# Fastino_DIOT_Connectors_P1_P6.net
KiCad netlist of a schematic drawn in Altium Designer
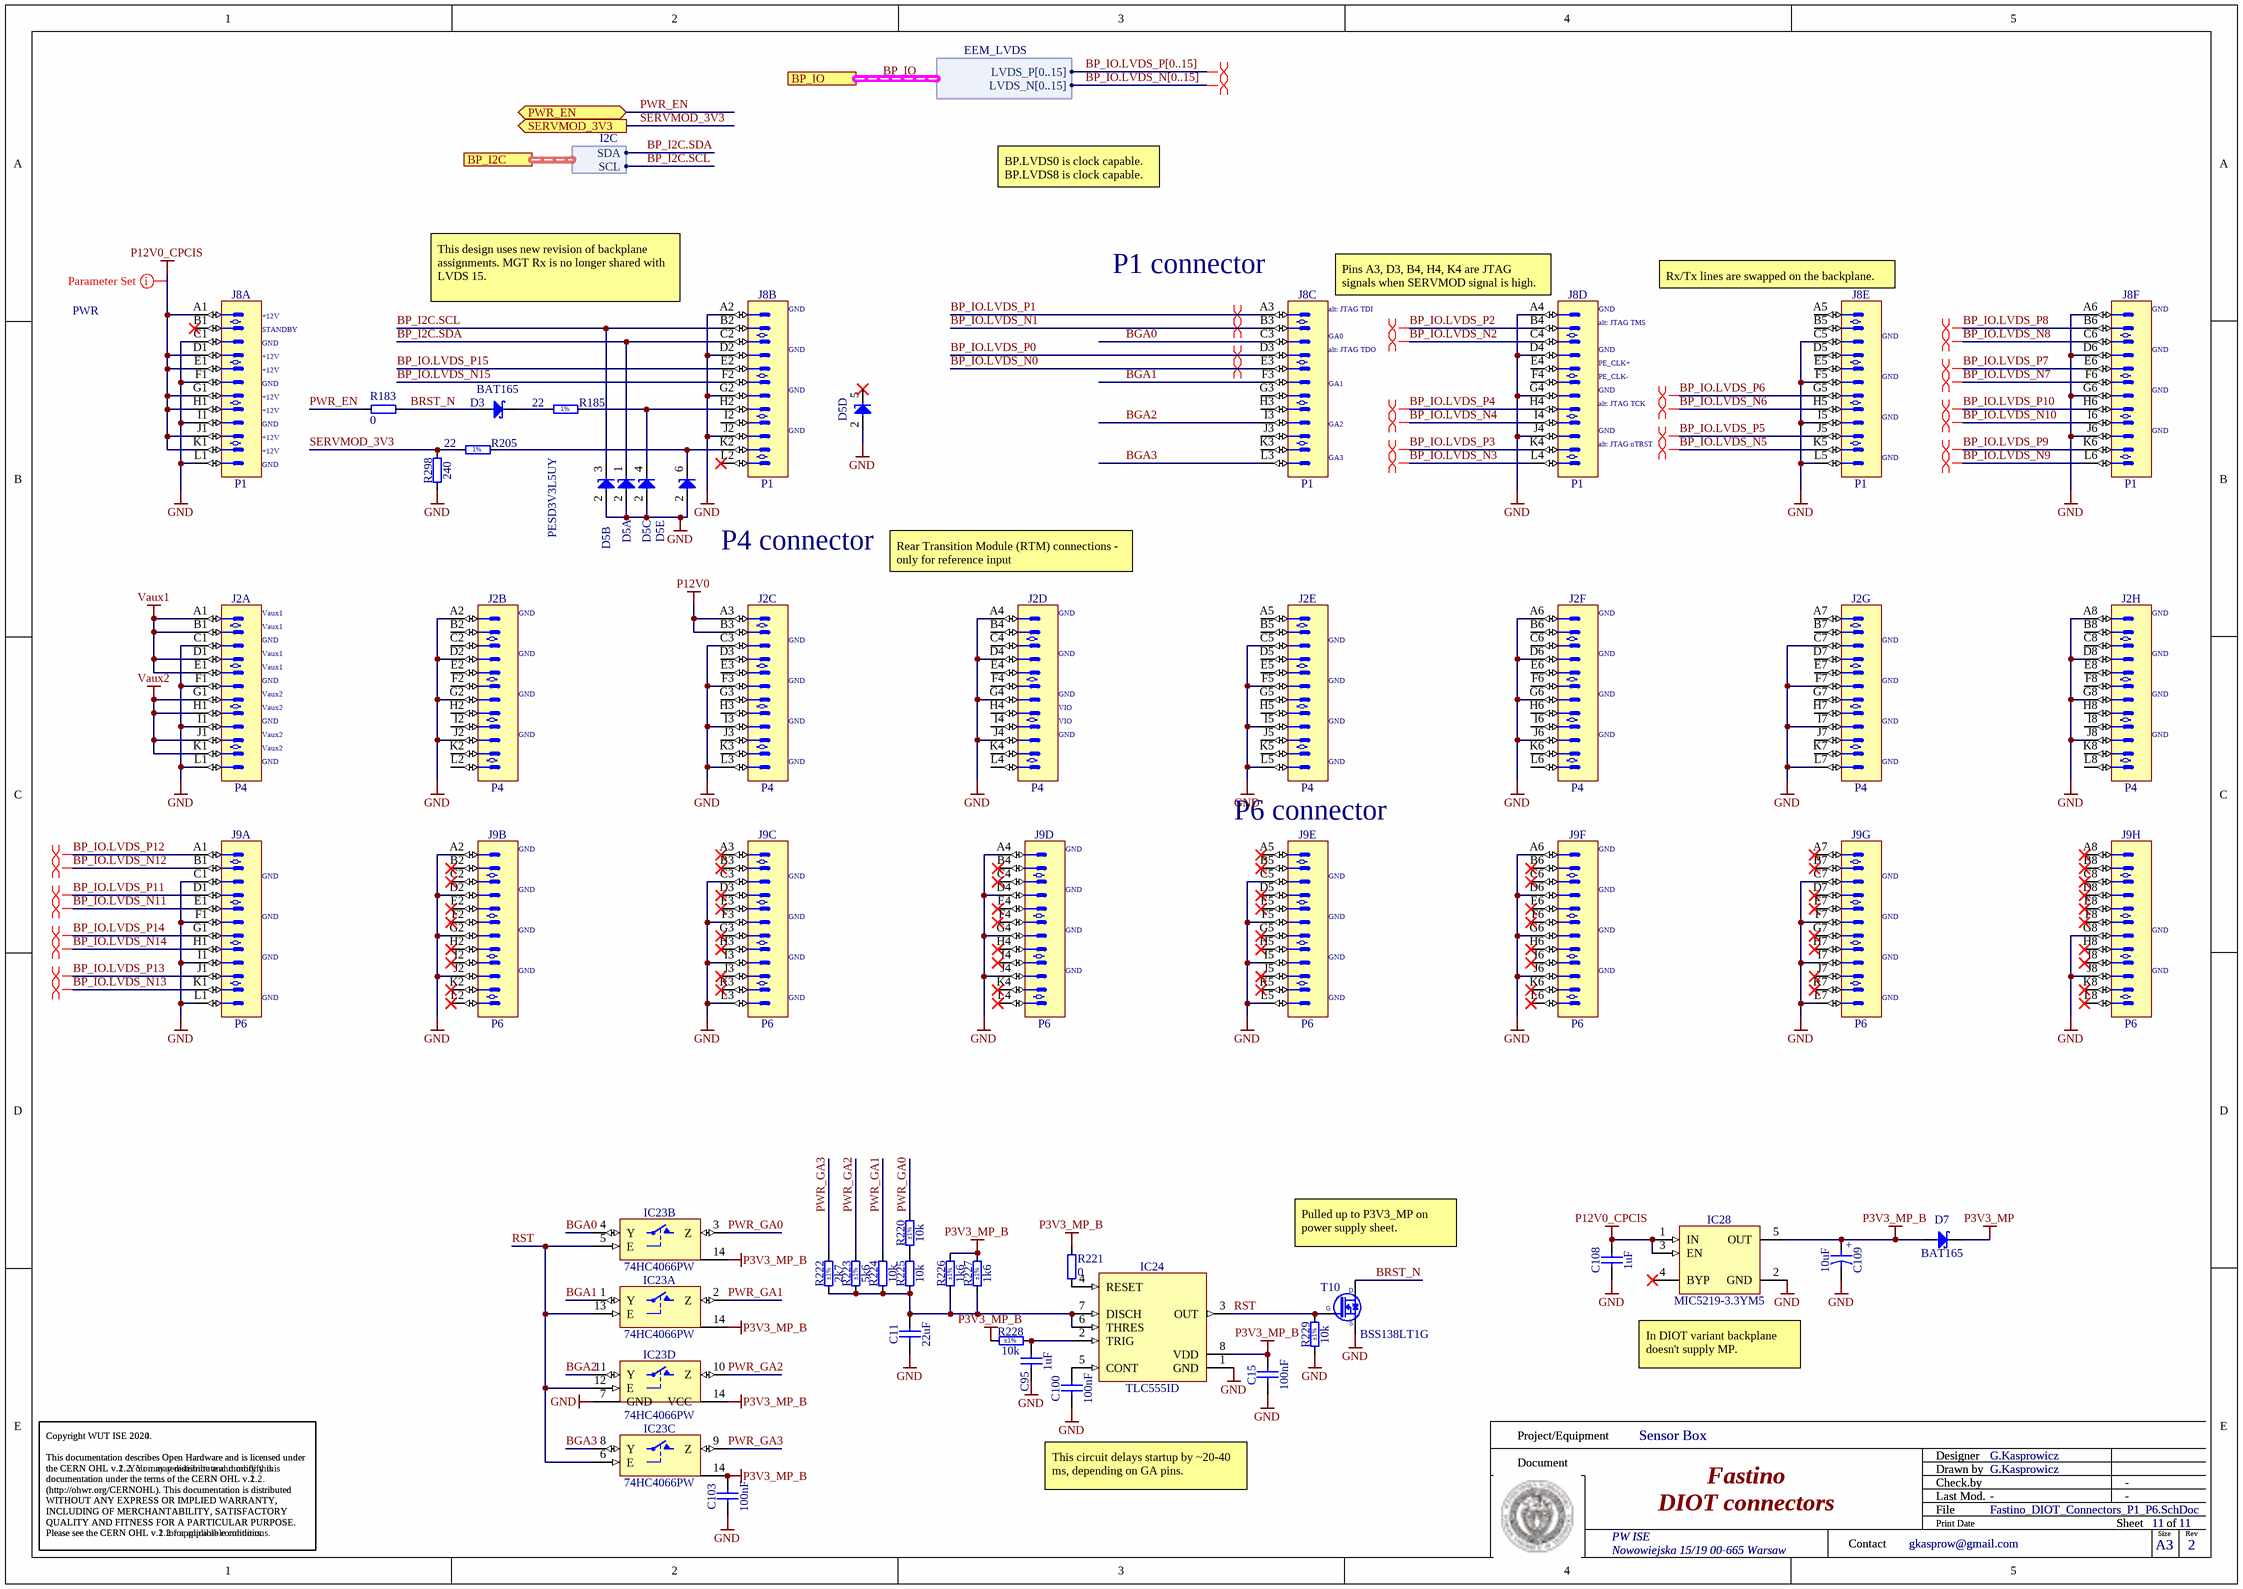
[diagram p0: Fastino_DIOT_Connectors_P1_P6.SchDoc]

(export (version "E")
  (design (tool "Eeschema 10.0.6"))
  (components
    (comp (ref "C11")
      (value "22uF")
      (footprint "CAPC1608X90N")
      (description "Non-polarised capacitor")
      (fields
        (field (name "MANUFACTURER") "GENERIC")
        (field (name "PART NUMBER") "CC0603_22UF_6.3V_20%_X5R")
        (field (name "AUTHOR") "CERN DEM JLC")
      )
      (libsource (lib "Capacitors") (part "Capacitor - non polarized"))
    )
    (comp (ref "C15")
      (value "100nF")
      (footprint "CAPC1005X55N")
      (description "Non-polarised capacitor")
      (fields
        (field (name "PART NUMBER") "CC0402_100NF_16V_10%_X5R")
        (field (name "VOLTAGE") "16V")
        (field (name "AUTHOR") "CERN DEM JLC")
      )
      (libsource (lib "Capacitors") (part "Capacitor - non polarized"))
    )
    (comp (ref "C95")
      (value "1uF")
      (footprint "CAPC1005X55N")
      (description "Non-polarised capacitor")
      (fields
        (field (name "PART NUMBER") "CC0402_1UF_16V_10%_X5R")
        (field (name "VOLTAGE") "16V")
        (field (name "AUTHOR") "CERN DEM JLC")
      )
      (libsource (lib "Capacitors") (part "Capacitor - non polarized"))
    )
    (comp (ref "C100")
      (value "100nF")
      (footprint "CAPC1005X55N")
      (description "Non-polarised capacitor")
      (fields
        (field (name "PART NUMBER") "CC0402_100NF_16V_10%_X5R")
        (field (name "VOLTAGE") "16V")
        (field (name "AUTHOR") "CERN DEM JLC")
      )
      (libsource (lib "Capacitors") (part "Capacitor - non polarized"))
    )
    (comp (ref "C103")
      (value "100nF")
      (footprint "CAPC1005X55N")
      (description "Non-polarised capacitor")
      (fields
        (field (name "PART NUMBER") "CC0402_100NF_16V_10%_X5R")
        (field (name "VOLTAGE") "16V")
        (field (name "AUTHOR") "CERN DEM JLC")
      )
      (libsource (lib "Capacitors") (part "Capacitor - non polarized"))
    )
    (comp (ref "C108")
      (value "1uF")
      (footprint "CAPC1608X87N")
      (description "Non-polarised capacitor")
      (fields
        (field (name "PART NUMBER") "CC0603_1UF_25V_10%_X7R")
        (field (name "VOLTAGE") "25V")
        (field (name "AUTHOR") "CERN DEM JLC")
      )
      (libsource (lib "Capacitors") (part "Capacitor - non polarized"))
    )
    (comp (ref "C109")
      (value "10uF")
      (footprint "CAPMP3216X180N")
      (description "Polarised capacitor")
      (fields
        (field (name "PART NUMBER") "CTE3216-18_10UF_16V_20%_AVX_TCJ")
        (field (name "VOLTAGE") "16V")
        (field (name "AUTHOR") "CERN DEM JLC")
      )
      (libsource (lib "Capacitors") (part "Capacitor - polarized"))
    )
    (comp (ref "D3")
      (value "BAT165")
      (footprint "SOD2512X110N")
      (description "Schottky Diode")
      (fields
        (field (name "MANUFACTURER") "INFINEON")
        (field (name "VOLTAGE") "40V")
        (field (name "AUTHOR") "CERN DEM JLC")
      )
      (libsource (lib "ICs And Semiconductors") (part "Diode Schottky"))
    )
    (comp (ref "D5")
      (value "PESD3V3L5UY")
      (footprint "SOT65P210X110-6N")
      (description "Fivefold ESD Protection Diode Arrays")
      (fields
        (field (name "VOLTAGE") "3.3V")
        (field (name "POWER") "200W")
        (field (name "AUTHOR") "CERN DEM WB")
      )
      (libsource (lib "ICs And Semiconductors") (part "PESD Array 5diodes 6pins Common anode2"))
    )
    (comp (ref "D7")
      (value "BAT165")
      (footprint "SOD2512X110N")
      (description "Schottky Diode")
      (fields
        (field (name "MANUFACTURER") "INFINEON")
        (field (name "VOLTAGE") "40V")
        (field (name "AUTHOR") "CERN DEM JLC")
      )
      (libsource (lib "ICs And Semiconductors") (part "Diode Schottky"))
    )
    (comp (ref "IC23")
      (value "74HC4066PW")
      (footprint "SOP65P640X110-14N")
      (fields (field (name "MANUFACTURER") "NXP SEMICONDUCTORS") (field (name "AUTHOR") "CERN DEM JLC"))
      (libsource (lib "ICs And Semiconductors") (part "4066"))
    )
    (comp (ref "IC24")
      (value "TLC555ID")
      (footprint "SOIC127P600X175-8N")
      (description "LinCMOS Timer")
      (fields (field (name "MANUFACTURER") "TEXAS INSTRUMENTS") (field (name "AUTHOR") "CERN DEM JMW"))
      (libsource (lib "ICs And Semiconductors") (part "TLC555"))
    )
    (comp (ref "IC28")
      (value "MIC5219-3.3YM5")
      (footprint "SOT95P280X145-5N")
      (description "500mA Peak Output LDO Regulator")
      (fields (field (name "MANUFACTURER") "MICROCHIP TECHNOLOGY") (field (name "AUTHOR") "CERN DEM WB"))
      (libsource (lib "ICs And Semiconductors") (part "MIC5219-X.XYM5"))
    )
    (comp (ref "J2")
      (value "P4")
      (footprint "AMPHENOL_10052837-101LF")
      (description "96 Contacts Header, 8 Columns, 4 Pairs per Column")
      (fields
        (field (name "PART NUMBER") "AMPHENOL_10052837-101LF")
        (field (name "MANUFACTURER") "AMPHENOL")
        (field (name "AUTHOR") "CERN DEM MR")
      )
      (libsource (lib "Connectors") (part "AMPHENOL_10052837-101LF"))
    )
    (comp (ref "J8")
      (value "P1")
      (footprint "AMPHENOL_10052825-101LF")
      (description "72 Contacts Header, 6 Columns, 4 Pairs per Column")
      (fields
        (field (name "PART NUMBER") "AMPHENOL_10052825-101LF")
        (field (name "MANUFACTURER") "AMPHENOL")
        (field (name "AUTHOR") "CERN DEM MR")
      )
      (libsource (lib "Connectors") (part "AMPHENOL_10052825-101LF"))
    )
    (comp (ref "J9")
      (value "P6")
      (footprint "AMPHENOL_10052838-101LF")
      (description "96 Contacts Header, 8 Columns, 4 Pairs per Column")
      (fields
        (field (name "PART NUMBER") "AMPHENOL_10052838-101LF")
        (field (name "MANUFACTURER") "AMPHENOL")
        (field (name "AUTHOR") "CERN DEM MR")
      )
      (libsource (lib "Connectors") (part "AMPHENOL_10052838-101LF"))
    )
    (comp (ref "R183")
      (value "0")
      (footprint "RESC1005X40N")
      (description "Resistor")
      (fields
        (field (name "PART NUMBER") "R0402_0R_JUMPER")
        (field (name "MANUFACTURER") "GENERIC")
        (field (name "AUTHOR") "CERN DEM JLC")
      )
      (libsource (lib "Resistors") (part "Resistor"))
    )
    (comp (ref "R185")
      (value "22")
      (footprint "RESC1005X40N")
      (description "Resistor - 1%")
      (fields
        (field (name "PART NUMBER") "R0402_22R_1%_0.0625W_100PPM")
        (field (name "POWER") "0.0625W")
        (field (name "AUTHOR") "CERN DEM JLC")
      )
      (libsource (lib "Resistors") (part "Resistor - 1%"))
    )
    (comp (ref "R205")
      (value "22")
      (footprint "RESC1005X40N")
      (description "Resistor - 1%")
      (fields
        (field (name "PART NUMBER") "R0402_22R_1%_0.0625W_100PPM")
        (field (name "POWER") "0.0625W")
        (field (name "AUTHOR") "CERN DEM JLC")
      )
      (libsource (lib "Resistors") (part "Resistor - 1%"))
    )
    (comp (ref "R220")
      (value "10k")
      (footprint "RESC1005X40N")
      (description "Resistor - 1%")
      (fields
        (field (name "PART NUMBER") "R0402_10K_1%_0.0625W_100PPM")
        (field (name "POWER") "0.0625W")
        (field (name "TOLERANCE") "±1%")
        (field (name "AUTHOR") "CERN DEM JLC")
      )
      (libsource (lib "Resistors") (part "Resistor - 1%"))
    )
    (comp (ref "R221")
      (value "0")
      (footprint "RESC1005X40N")
      (description "Resistor")
      (fields
        (field (name "PART NUMBER") "R0402_0R_JUMPER")
        (field (name "MANUFACTURER") "GENERIC")
        (field (name "AUTHOR") "CERN DEM JLC")
      )
      (libsource (lib "Resistors") (part "Resistor"))
    )
    (comp (ref "R222")
      (value "2k7")
      (footprint "RESC1608X55N")
      (description "Resistor - 1%")
      (fields
        (field (name "PART NUMBER") "R0603_2K7_1%_0.1W_100PPM")
        (field (name "POWER") "0.1W")
        (field (name "TOLERANCE") "±1%")
        (field (name "AUTHOR") "CERN DEM JLC")
      )
      (libsource (lib "") (part "Resistor - 1%_1"))
    )
    (comp (ref "R223")
      (value "5k6")
      (footprint "RESC1005X40N")
      (description "Resistor - 1%")
      (fields
        (field (name "PART NUMBER") "R0402_5K6_1%_0.0625W_100PPM")
        (field (name "POWER") "0.0625W")
        (field (name "TOLERANCE") "±1%")
        (field (name "AUTHOR") "CERN DEM JLC")
      )
      (libsource (lib "Resistors") (part "Resistor - 1%"))
    )
    (comp (ref "R224")
      (value "10k")
      (footprint "RESC1005X40N")
      (description "Resistor - 1%")
      (fields
        (field (name "PART NUMBER") "R0402_10K_1%_0.0625W_100PPM")
        (field (name "POWER") "0.0625W")
        (field (name "AUTHOR") "CERN DEM JLC")
      )
      (libsource (lib "Resistors") (part "Resistor - 1%"))
    )
    (comp (ref "R225")
      (value "10k")
      (footprint "RESC1005X40N")
      (description "Resistor - 1%")
      (fields
        (field (name "PART NUMBER") "R0402_10K_1%_0.0625W_100PPM")
        (field (name "POWER") "0.0625W")
        (field (name "AUTHOR") "CERN DEM JLC")
      )
      (libsource (lib "Resistors") (part "Resistor - 1%"))
    )
    (comp (ref "R226")
      (value "1k6")
      (footprint "RESC1005X40N")
      (description "Resistor - 1%")
      (fields
        (field (name "PART NUMBER") "R0402_1K6_1%_0.0625W_100PPM")
        (field (name "POWER") "0.0625W")
        (field (name "TOLERANCE") "±1%")
        (field (name "AUTHOR") "CERN DEM JLC")
      )
      (libsource (lib "Resistors") (part "Resistor - 1%"))
    )
    (comp (ref "R227")
      (value "1k6")
      (footprint "RESC1005X40N")
      (description "Resistor - 1%")
      (fields
        (field (name "PART NUMBER") "R0402_1K6_1%_0.0625W_100PPM")
        (field (name "POWER") "0.0625W")
        (field (name "TOLERANCE") "±1%")
        (field (name "AUTHOR") "CERN DEM JLC")
      )
      (libsource (lib "Resistors") (part "Resistor - 1%"))
    )
    (comp (ref "R228")
      (value "10k")
      (footprint "RESC1005X40N")
      (description "Resistor - 1%")
      (fields
        (field (name "TOLERANCE") "±1%")
        (field (name "PART NUMBER") "R0402_10K_1%_0.0625W_100PPM")
        (field (name "POWER") "0.0625W")
        (field (name "AUTHOR") "CERN DEM JLC")
      )
      (libsource (lib "Resistors") (part "Resistor - 1%"))
    )
    (comp (ref "R229")
      (value "10k")
      (footprint "RESC1005X40N")
      (description "Resistor - 1%")
      (fields
        (field (name "TOLERANCE") "±1%")
        (field (name "PART NUMBER") "R0402_10K_1%_0.0625W_100PPM")
        (field (name "POWER") "0.0625W")
        (field (name "AUTHOR") "CERN DEM JLC")
      )
      (libsource (lib "Resistors") (part "Resistor - 1%"))
    )
    (comp (ref "R298")
      (value "240")
      (footprint "RESC1005X40N")
      (description "Resistor - 1%")
      (fields
        (field (name "PART NUMBER") "R0402_240R_1%_0.0625W_100PPM")
        (field (name "POWER") "0.0625W")
        (field (name "AUTHOR") "CERN DEM JLC")
      )
      (libsource (lib "Resistors") (part "Resistor - 1%"))
    )
    (comp (ref "T10")
      (value "BSS138LT1G")
      (footprint "SOT95P240X110-3N")
      (description "N-CHANNEL MOSFET WITH DIODE")
      (fields (field (name "MANUFACTURER") "ON SEMICONDUCTOR") (field (name "AUTHOR") "CERN DEM JLC"))
      (libsource (lib "ICs And Semiconductors") (part "N-MOSFET-D 1G 2S 3D"))
    )
  )
  (nets
    (net (code "3") (name "/BGA0") (class "Default")
      (node (ref "IC23") (pin "4") (pinfunction "Y_4") (pintype "bidirectional"))
      (node (ref "J8") (pin "C3") (pinfunction "C3_C3") (pintype "bidirectional"))
    )
    (net (code "4") (name "/BGA1") (class "Default")
      (node (ref "IC23") (pin "1") (pinfunction "Y_1") (pintype "bidirectional"))
      (node (ref "J8") (pin "F3") (pinfunction "F3_F3") (pintype "bidirectional"))
    )
    (net (code "5") (name "/BGA2") (class "Default")
      (node (ref "IC23") (pin "11") (pinfunction "Y_11") (pintype "bidirectional"))
      (node (ref "J8") (pin "I3") (pinfunction "I3_I3") (pintype "bidirectional"))
    )
    (net (code "6") (name "/BGA3") (class "Default")
      (node (ref "IC23") (pin "8") (pinfunction "Y_8") (pintype "bidirectional"))
      (node (ref "J8") (pin "L3") (pinfunction "L3_L3") (pintype "bidirectional"))
    )
    (net (code "7") (name "/BP_I2C.SCL") (class "Default")
      (node (ref "D5") (pin "3") (pinfunction "C_3") (pintype "passive"))
      (node (ref "J8") (pin "B2") (pinfunction "B2_B2") (pintype "bidirectional"))
    )
    (net (code "8") (name "/BP_I2C.SDA") (class "Default")
      (node (ref "D5") (pin "1") (pinfunction "C_1") (pintype "passive"))
      (node (ref "J8") (pin "C2") (pinfunction "C2_C2") (pintype "bidirectional"))
    )
    (net (code "9") (name "/BP_IO.LVDS_N0") (class "Default")
      (node (ref "J8") (pin "E3") (pinfunction "E3_E3") (pintype "bidirectional"))
    )
    (net (code "10") (name "/BP_IO.LVDS_N1") (class "Default")
      (node (ref "J8") (pin "B3") (pinfunction "B3_B3") (pintype "bidirectional"))
    )
    (net (code "11") (name "/BP_IO.LVDS_N2") (class "Default")
      (node (ref "J8") (pin "C4") (pinfunction "C4_C4") (pintype "bidirectional"))
    )
    (net (code "12") (name "/BP_IO.LVDS_N3") (class "Default")
      (node (ref "J8") (pin "L4") (pinfunction "L4_L4") (pintype "bidirectional"))
    )
    (net (code "13") (name "/BP_IO.LVDS_N4") (class "Default")
      (node (ref "J8") (pin "I4") (pinfunction "I4_I4") (pintype "bidirectional"))
    )
    (net (code "14") (name "/BP_IO.LVDS_N5") (class "Default")
      (node (ref "J8") (pin "K5") (pinfunction "K5_K5") (pintype "bidirectional"))
    )
    (net (code "15") (name "/BP_IO.LVDS_N6") (class "Default")
      (node (ref "J8") (pin "H5") (pinfunction "H5_H5") (pintype "bidirectional"))
    )
    (net (code "16") (name "/BP_IO.LVDS_N7") (class "Default")
      (node (ref "J8") (pin "F6") (pinfunction "F6_F6") (pintype "bidirectional"))
    )
    (net (code "17") (name "/BP_IO.LVDS_N8") (class "Default")
      (node (ref "J8") (pin "C6") (pinfunction "C6_C6") (pintype "bidirectional"))
    )
    (net (code "18") (name "/BP_IO.LVDS_N9") (class "Default")
      (node (ref "J8") (pin "L6") (pinfunction "L6_L6") (pintype "bidirectional"))
    )
    (net (code "19") (name "/BP_IO.LVDS_N10") (class "Default")
      (node (ref "J8") (pin "I6") (pinfunction "I6_I6") (pintype "bidirectional"))
    )
    (net (code "20") (name "/BP_IO.LVDS_N11") (class "Default")
      (node (ref "J9") (pin "E1") (pinfunction "E1_E1") (pintype "bidirectional"))
    )
    (net (code "21") (name "/BP_IO.LVDS_N12") (class "Default")
      (node (ref "J9") (pin "B1") (pinfunction "B1_B1") (pintype "bidirectional"))
    )
    (net (code "22") (name "/BP_IO.LVDS_N13") (class "Default")
      (node (ref "J9") (pin "K1") (pinfunction "K1_K1") (pintype "bidirectional"))
    )
    (net (code "23") (name "/BP_IO.LVDS_N14") (class "Default")
      (node (ref "J9") (pin "H1") (pinfunction "H1_H1") (pintype "bidirectional"))
    )
    (net (code "24") (name "/BP_IO.LVDS_N15") (class "Default")
      (node (ref "J8") (pin "F2") (pinfunction "F2_F2") (pintype "bidirectional"))
    )
    (net (code "26") (name "/BP_IO.LVDS_P0") (class "Default")
      (node (ref "J8") (pin "D3") (pinfunction "D3_D3") (pintype "bidirectional"))
    )
    (net (code "27") (name "/BP_IO.LVDS_P1") (class "Default")
      (node (ref "J8") (pin "A3") (pinfunction "A3_A3") (pintype "bidirectional"))
    )
    (net (code "28") (name "/BP_IO.LVDS_P2") (class "Default")
      (node (ref "J8") (pin "B4") (pinfunction "B4_B4") (pintype "bidirectional"))
    )
    (net (code "29") (name "/BP_IO.LVDS_P3") (class "Default")
      (node (ref "J8") (pin "K4") (pinfunction "K4_K4") (pintype "bidirectional"))
    )
    (net (code "30") (name "/BP_IO.LVDS_P4") (class "Default")
      (node (ref "J8") (pin "H4") (pinfunction "H4_H4") (pintype "bidirectional"))
    )
    (net (code "31") (name "/BP_IO.LVDS_P5") (class "Default")
      (node (ref "J8") (pin "J5") (pinfunction "J5_J5") (pintype "bidirectional"))
    )
    (net (code "32") (name "/BP_IO.LVDS_P6") (class "Default")
      (node (ref "J8") (pin "G5") (pinfunction "G5_G5") (pintype "bidirectional"))
    )
    (net (code "33") (name "/BP_IO.LVDS_P7") (class "Default")
      (node (ref "J8") (pin "E6") (pinfunction "E6_E6") (pintype "bidirectional"))
    )
    (net (code "34") (name "/BP_IO.LVDS_P8") (class "Default")
      (node (ref "J8") (pin "B6") (pinfunction "B6_B6") (pintype "bidirectional"))
    )
    (net (code "35") (name "/BP_IO.LVDS_P9") (class "Default")
      (node (ref "J8") (pin "K6") (pinfunction "K6_K6") (pintype "bidirectional"))
    )
    (net (code "36") (name "/BP_IO.LVDS_P10") (class "Default")
      (node (ref "J8") (pin "H6") (pinfunction "H6_H6") (pintype "bidirectional"))
    )
    (net (code "37") (name "/BP_IO.LVDS_P11") (class "Default")
      (node (ref "J9") (pin "D1") (pinfunction "D1_D1") (pintype "bidirectional"))
    )
    (net (code "38") (name "/BP_IO.LVDS_P12") (class "Default")
      (node (ref "J9") (pin "A1") (pinfunction "A1_A1") (pintype "bidirectional"))
    )
    (net (code "39") (name "/BP_IO.LVDS_P13") (class "Default")
      (node (ref "J9") (pin "J1") (pinfunction "J1_J1") (pintype "bidirectional"))
    )
    (net (code "40") (name "/BP_IO.LVDS_P14") (class "Default")
      (node (ref "J9") (pin "G1") (pinfunction "G1_G1") (pintype "bidirectional"))
    )
    (net (code "41") (name "/BP_IO.LVDS_P15") (class "Default")
      (node (ref "J8") (pin "E2") (pinfunction "E2_E2") (pintype "bidirectional"))
    )
    (net (code "44") (name "/BRST_N") (class "Default")
      (node (ref "D3") (pin "2") (pinfunction "A_2") (pintype "passive"))
      (node (ref "R183") (pin "1") (pinfunction "1_1") (pintype "passive"))
      (node (ref "T10") (pin "3") (pinfunction "D_3") (pintype "passive"))
    )
    (net (code "45") (name "/PWR_EN") (class "Default")
      (node (ref "R183") (pin "2") (pinfunction "2_2") (pintype "passive"))
    )
    (net (code "46") (name "/PWR_GA0") (class "Default")
      (node (ref "IC23") (pin "3") (pinfunction "Z_3") (pintype "bidirectional"))
      (node (ref "R220") (pin "2") (pinfunction "2_2") (pintype "passive"))
    )
    (net (code "47") (name "/PWR_GA1") (class "Default")
      (node (ref "IC23") (pin "2") (pinfunction "Z_2") (pintype "bidirectional"))
      (node (ref "R224") (pin "2") (pinfunction "2_2") (pintype "passive"))
    )
    (net (code "48") (name "/PWR_GA2") (class "Default")
      (node (ref "IC23") (pin "10") (pinfunction "Z_10") (pintype "bidirectional"))
      (node (ref "R223") (pin "2") (pinfunction "2_2") (pintype "passive"))
    )
    (net (code "49") (name "/PWR_GA3") (class "Default")
      (node (ref "IC23") (pin "9") (pinfunction "Z_9") (pintype "bidirectional"))
      (node (ref "R222") (pin "2") (pinfunction "2_2") (pintype "passive"))
    )
    (net (code "50") (name "/RST") (class "Default")
      (node (ref "IC23") (pin "12") (pinfunction "E_12") (pintype "input"))
      (node (ref "IC23") (pin "13") (pinfunction "E_13") (pintype "input"))
      (node (ref "IC23") (pin "5") (pinfunction "E_5") (pintype "input"))
      (node (ref "IC23") (pin "6") (pinfunction "E_6") (pintype "input"))
      (node (ref "IC24") (pin "3") (pinfunction "OUT_3") (pintype "output"))
      (node (ref "R229") (pin "2") (pinfunction "2_2") (pintype "passive"))
      (node (ref "T10") (pin "1") (pinfunction "G_1") (pintype "passive"))
    )
    (net (code "51") (name "/SERVMOD_3V3") (class "Default")
      (node (ref "R205") (pin "1") (pinfunction "1_1") (pintype "passive"))
      (node (ref "R298") (pin "2") (pinfunction "2_2") (pintype "passive"))
    )
    (net (code "53") (name "GND") (class "Default")
      (node (ref "C100") (pin "1") (pinfunction "1_1") (pintype "passive"))
      (node (ref "C103") (pin "1") (pinfunction "1_1") (pintype "passive"))
      (node (ref "C108") (pin "1") (pinfunction "1_1") (pintype "passive"))
      (node (ref "C109") (pin "2") (pinfunction "2_2") (pintype "passive"))
      (node (ref "C11") (pin "1") (pinfunction "1_1") (pintype "passive"))
      (node (ref "C15") (pin "1") (pinfunction "1_1") (pintype "passive"))
      (node (ref "C95") (pin "1") (pinfunction "1_1") (pintype "passive"))
      (node (ref "D5") (pin "2") (pinfunction "A_2") (pintype "passive"))
      (node (ref "IC23") (pin "7") (pinfunction "GND_7") (pintype "power_in"))
      (node (ref "IC24") (pin "1") (pinfunction "GND_1") (pintype "power_in"))
      (node (ref "IC28") (pin "2") (pinfunction "GND_2") (pintype "power_in"))
      (node (ref "J2") (pin "A2") (pinfunction "A2_A2") (pintype "bidirectional"))
      (node (ref "J2") (pin "A4") (pinfunction "A4_A4") (pintype "bidirectional"))
      (node (ref "J2") (pin "A6") (pinfunction "A6_A6") (pintype "bidirectional"))
      (node (ref "J2") (pin "A8") (pinfunction "A8_A8") (pintype "bidirectional"))
      (node (ref "J2") (pin "C1") (pinfunction "C1_C1") (pintype "bidirectional"))
      (node (ref "J2") (pin "C3") (pinfunction "C3_C3") (pintype "bidirectional"))
      (node (ref "J2") (pin "C5") (pinfunction "C5_C5") (pintype "bidirectional"))
      (node (ref "J2") (pin "C7") (pinfunction "C7_C7") (pintype "bidirectional"))
      (node (ref "J2") (pin "D2") (pinfunction "D2_D2") (pintype "bidirectional"))
      (node (ref "J2") (pin "D4") (pinfunction "D4_D4") (pintype "bidirectional"))
      (node (ref "J2") (pin "D6") (pinfunction "D6_D6") (pintype "bidirectional"))
      (node (ref "J2") (pin "D8") (pinfunction "D8_D8") (pintype "bidirectional"))
      (node (ref "J2") (pin "F1") (pinfunction "F1_F1") (pintype "bidirectional"))
      (node (ref "J2") (pin "F3") (pinfunction "F3_F3") (pintype "bidirectional"))
      (node (ref "J2") (pin "F5") (pinfunction "F5_F5") (pintype "bidirectional"))
      (node (ref "J2") (pin "F7") (pinfunction "F7_F7") (pintype "bidirectional"))
      (node (ref "J2") (pin "G2") (pinfunction "G2_G2") (pintype "bidirectional"))
      (node (ref "J2") (pin "G4") (pinfunction "G4_G4") (pintype "bidirectional"))
      (node (ref "J2") (pin "G6") (pinfunction "G6_G6") (pintype "bidirectional"))
      (node (ref "J2") (pin "G8") (pinfunction "G8_G8") (pintype "bidirectional"))
      (node (ref "J2") (pin "I1") (pinfunction "I1_I1") (pintype "bidirectional"))
      (node (ref "J2") (pin "I3") (pinfunction "I3_I3") (pintype "bidirectional"))
      (node (ref "J2") (pin "I5") (pinfunction "I5_I5") (pintype "bidirectional"))
      (node (ref "J2") (pin "I7") (pinfunction "I7_I7") (pintype "bidirectional"))
      (node (ref "J2") (pin "J2") (pinfunction "J2_J2") (pintype "bidirectional"))
      (node (ref "J2") (pin "J4") (pinfunction "J4_J4") (pintype "bidirectional"))
      (node (ref "J2") (pin "J6") (pinfunction "J6_J6") (pintype "bidirectional"))
      (node (ref "J2") (pin "J8") (pinfunction "J8_J8") (pintype "bidirectional"))
      (node (ref "J2") (pin "L1") (pinfunction "L1_L1") (pintype "bidirectional"))
      (node (ref "J2") (pin "L3") (pinfunction "L3_L3") (pintype "bidirectional"))
      (node (ref "J2") (pin "L5") (pinfunction "L5_L5") (pintype "bidirectional"))
      (node (ref "J2") (pin "L7") (pinfunction "L7_L7") (pintype "bidirectional"))
      (node (ref "J8") (pin "A2") (pinfunction "A2_A2") (pintype "bidirectional"))
      (node (ref "J8") (pin "A4") (pinfunction "A4_A4") (pintype "bidirectional"))
      (node (ref "J8") (pin "A6") (pinfunction "A6_A6") (pintype "bidirectional"))
      (node (ref "J8") (pin "C1") (pinfunction "C1_C1") (pintype "bidirectional"))
      (node (ref "J8") (pin "C5") (pinfunction "C5_C5") (pintype "bidirectional"))
      (node (ref "J8") (pin "D2") (pinfunction "D2_D2") (pintype "bidirectional"))
      (node (ref "J8") (pin "D4") (pinfunction "D4_D4") (pintype "bidirectional"))
      (node (ref "J8") (pin "D6") (pinfunction "D6_D6") (pintype "bidirectional"))
      (node (ref "J8") (pin "F1") (pinfunction "F1_F1") (pintype "bidirectional"))
      (node (ref "J8") (pin "F5") (pinfunction "F5_F5") (pintype "bidirectional"))
      (node (ref "J8") (pin "G2") (pinfunction "G2_G2") (pintype "bidirectional"))
      (node (ref "J8") (pin "G4") (pinfunction "G4_G4") (pintype "bidirectional"))
      (node (ref "J8") (pin "G6") (pinfunction "G6_G6") (pintype "bidirectional"))
      (node (ref "J8") (pin "I1") (pinfunction "I1_I1") (pintype "bidirectional"))
      (node (ref "J8") (pin "I5") (pinfunction "I5_I5") (pintype "bidirectional"))
      (node (ref "J8") (pin "J2") (pinfunction "J2_J2") (pintype "bidirectional"))
      (node (ref "J8") (pin "J4") (pinfunction "J4_J4") (pintype "bidirectional"))
      (node (ref "J8") (pin "J6") (pinfunction "J6_J6") (pintype "bidirectional"))
      (node (ref "J8") (pin "L1") (pinfunction "L1_L1") (pintype "bidirectional"))
      (node (ref "J8") (pin "L5") (pinfunction "L5_L5") (pintype "bidirectional"))
      (node (ref "J9") (pin "A2") (pinfunction "A2_A2") (pintype "bidirectional"))
      (node (ref "J9") (pin "A4") (pinfunction "A4_A4") (pintype "bidirectional"))
      (node (ref "J9") (pin "A6") (pinfunction "A6_A6") (pintype "bidirectional"))
      (node (ref "J9") (pin "C1") (pinfunction "C1_C1") (pintype "bidirectional"))
      (node (ref "J9") (pin "C3") (pinfunction "C3_C3") (pintype "bidirectional"))
      (node (ref "J9") (pin "C5") (pinfunction "C5_C5") (pintype "bidirectional"))
      (node (ref "J9") (pin "C7") (pinfunction "C7_C7") (pintype "bidirectional"))
      (node (ref "J9") (pin "D2") (pinfunction "D2_D2") (pintype "bidirectional"))
      (node (ref "J9") (pin "D4") (pinfunction "D4_D4") (pintype "bidirectional"))
      (node (ref "J9") (pin "D6") (pinfunction "D6_D6") (pintype "bidirectional"))
      (node (ref "J9") (pin "F1") (pinfunction "F1_F1") (pintype "bidirectional"))
      (node (ref "J9") (pin "F3") (pinfunction "F3_F3") (pintype "bidirectional"))
      (node (ref "J9") (pin "F5") (pinfunction "F5_F5") (pintype "bidirectional"))
      (node (ref "J9") (pin "F7") (pinfunction "F7_F7") (pintype "bidirectional"))
      (node (ref "J9") (pin "G2") (pinfunction "G2_G2") (pintype "bidirectional"))
      (node (ref "J9") (pin "G4") (pinfunction "G4_G4") (pintype "bidirectional"))
      (node (ref "J9") (pin "G6") (pinfunction "G6_G6") (pintype "bidirectional"))
      (node (ref "J9") (pin "G8") (pinfunction "G8_G8") (pintype "bidirectional"))
      (node (ref "J9") (pin "I1") (pinfunction "I1_I1") (pintype "bidirectional"))
      (node (ref "J9") (pin "I3") (pinfunction "I3_I3") (pintype "bidirectional"))
      (node (ref "J9") (pin "I5") (pinfunction "I5_I5") (pintype "bidirectional"))
      (node (ref "J9") (pin "I7") (pinfunction "I7_I7") (pintype "bidirectional"))
      (node (ref "J9") (pin "J2") (pinfunction "J2_J2") (pintype "bidirectional"))
      (node (ref "J9") (pin "J4") (pinfunction "J4_J4") (pintype "bidirectional"))
      (node (ref "J9") (pin "J6") (pinfunction "J6_J6") (pintype "bidirectional"))
      (node (ref "J9") (pin "J8") (pinfunction "J8_J8") (pintype "bidirectional"))
      (node (ref "J9") (pin "L1") (pinfunction "L1_L1") (pintype "bidirectional"))
      (node (ref "J9") (pin "L3") (pinfunction "L3_L3") (pintype "bidirectional"))
      (node (ref "J9") (pin "L5") (pinfunction "L5_L5") (pintype "bidirectional"))
      (node (ref "J9") (pin "L7") (pinfunction "L7_L7") (pintype "bidirectional"))
      (node (ref "R229") (pin "1") (pinfunction "1_1") (pintype "passive"))
      (node (ref "R298") (pin "1") (pinfunction "1_1") (pintype "passive"))
      (node (ref "T10") (pin "2") (pinfunction "S_2") (pintype "passive"))
    )
    (net (code "54") (name "Net-(D3-C)") (class "Default")
      (node (ref "D3") (pin "1") (pinfunction "C_1") (pintype "passive"))
      (node (ref "R185") (pin "1") (pinfunction "1_1") (pintype "passive"))
    )
    (net (code "55") (name "Net-(D5C-C)") (class "Default")
      (node (ref "D5") (pin "4") (pinfunction "C_4") (pintype "passive"))
      (node (ref "J8") (pin "H2") (pinfunction "H2_H2") (pintype "bidirectional"))
      (node (ref "R185") (pin "2") (pinfunction "2_2") (pintype "passive"))
    )
    (net (code "56") (name "Net-(D5E-C)") (class "Default")
      (node (ref "D5") (pin "6") (pinfunction "C_6") (pintype "passive"))
      (node (ref "J8") (pin "K2") (pinfunction "K2_K2") (pintype "bidirectional"))
      (node (ref "R205") (pin "2") (pinfunction "2_2") (pintype "passive"))
    )
    (net (code "57") (name "Net-(IC24-CONT)") (class "Default")
      (node (ref "C100") (pin "2") (pinfunction "2_2") (pintype "passive"))
      (node (ref "IC24") (pin "5") (pinfunction "CONT_5") (pintype "input"))
    )
    (net (code "58") (name "Net-(IC24-DISCH)") (class "Default")
      (node (ref "C11") (pin "2") (pinfunction "2_2") (pintype "passive"))
      (node (ref "IC24") (pin "6") (pinfunction "THRES_6") (pintype "input"))
      (node (ref "IC24") (pin "7") (pinfunction "DISCH_7") (pintype "input"))
      (node (ref "R222") (pin "1") (pinfunction "1_1") (pintype "passive"))
      (node (ref "R223") (pin "1") (pinfunction "1_1") (pintype "passive"))
      (node (ref "R224") (pin "1") (pinfunction "1_1") (pintype "passive"))
      (node (ref "R225") (pin "1") (pinfunction "1_1") (pintype "passive"))
      (node (ref "R226") (pin "1") (pinfunction "1_1") (pintype "passive"))
      (node (ref "R227") (pin "1") (pinfunction "1_1") (pintype "passive"))
    )
    (net (code "59") (name "Net-(IC24-RESET)") (class "Default")
      (node (ref "IC24") (pin "4") (pinfunction "RESET_4") (pintype "input"))
      (node (ref "R221") (pin "1") (pinfunction "1_1") (pintype "passive"))
    )
    (net (code "60") (name "Net-(IC24-TRIG)") (class "Default")
      (node (ref "C95") (pin "2") (pinfunction "2_2") (pintype "passive"))
      (node (ref "IC24") (pin "2") (pinfunction "TRIG_2") (pintype "input"))
      (node (ref "R228") (pin "2") (pinfunction "2_2") (pintype "passive"))
    )
    (net (code "61") (name "Net-(R220-Pad1)") (class "Default")
      (node (ref "R220") (pin "1") (pinfunction "1_1") (pintype "passive"))
      (node (ref "R225") (pin "2") (pinfunction "2_2") (pintype "passive"))
    )
    (net (code "62") (name "P3V3_MP") (class "Default")
      (node (ref "D7") (pin "1") (pinfunction "C_1") (pintype "passive"))
    )
    (net (code "63") (name "P3V3_MP_B") (class "Default")
      (node (ref "C103") (pin "2") (pinfunction "2_2") (pintype "passive"))
      (node (ref "C109") (pin "1") (pinfunction "1_1") (pintype "passive"))
      (node (ref "C15") (pin "2") (pinfunction "2_2") (pintype "passive"))
      (node (ref "D7") (pin "2") (pinfunction "A_2") (pintype "passive"))
      (node (ref "IC23") (pin "14") (pinfunction "VCC_14") (pintype "power_in"))
      (node (ref "IC24") (pin "8") (pinfunction "VDD_8") (pintype "power_in"))
      (node (ref "IC28") (pin "5") (pinfunction "OUT_5") (pintype "power_in"))
      (node (ref "R221") (pin "2") (pinfunction "2_2") (pintype "passive"))
      (node (ref "R226") (pin "2") (pinfunction "2_2") (pintype "passive"))
      (node (ref "R227") (pin "2") (pinfunction "2_2") (pintype "passive"))
      (node (ref "R228") (pin "1") (pinfunction "1_1") (pintype "passive"))
    )
    (net (code "64") (name "P12V0") (class "Default")
      (node (ref "J2") (pin "A3") (pinfunction "A3_A3") (pintype "bidirectional"))
      (node (ref "J2") (pin "B3") (pinfunction "B3_B3") (pintype "bidirectional"))
    )
    (net (code "65") (name "P12V0_CPCIS") (class "Default")
      (node (ref "C108") (pin "2") (pinfunction "2_2") (pintype "passive"))
      (node (ref "IC28") (pin "1") (pinfunction "IN_1") (pintype "input"))
      (node (ref "IC28") (pin "3") (pinfunction "EN_3") (pintype "input"))
      (node (ref "J8") (pin "A1") (pinfunction "A1_A1") (pintype "bidirectional"))
      (node (ref "J8") (pin "D1") (pinfunction "D1_D1") (pintype "bidirectional"))
      (node (ref "J8") (pin "E1") (pinfunction "E1_E1") (pintype "bidirectional"))
      (node (ref "J8") (pin "G1") (pinfunction "G1_G1") (pintype "bidirectional"))
      (node (ref "J8") (pin "H1") (pinfunction "H1_H1") (pintype "bidirectional"))
      (node (ref "J8") (pin "J1") (pinfunction "J1_J1") (pintype "bidirectional"))
      (node (ref "J8") (pin "K1") (pinfunction "K1_K1") (pintype "bidirectional"))
    )
    (net (code "66") (name "Vaux1") (class "Default")
      (node (ref "J2") (pin "A1") (pinfunction "A1_A1") (pintype "bidirectional"))
      (node (ref "J2") (pin "B1") (pinfunction "B1_B1") (pintype "bidirectional"))
      (node (ref "J2") (pin "D1") (pinfunction "D1_D1") (pintype "bidirectional"))
      (node (ref "J2") (pin "E1") (pinfunction "E1_E1") (pintype "bidirectional"))
    )
    (net (code "67") (name "Vaux2") (class "Default")
      (node (ref "J2") (pin "G1") (pinfunction "G1_G1") (pintype "bidirectional"))
      (node (ref "J2") (pin "H1") (pinfunction "H1_H1") (pintype "bidirectional"))
      (node (ref "J2") (pin "J1") (pinfunction "J1_J1") (pintype "bidirectional"))
      (node (ref "J2") (pin "K1") (pinfunction "K1_K1") (pintype "bidirectional"))
    )
    (net (code "68") (name "unconnected-(D5D-C-Pad5)") (class "Default")
      (node (ref "D5") (pin "5") (pinfunction "C_5") (pintype "passive+no_connect"))
    )
    (net (code "69") (name "unconnected-(IC28-BYP-Pad4)") (class "Default")
      (node (ref "IC28") (pin "4") (pinfunction "BYP_4") (pintype "passive+no_connect"))
    )
    (net (code "70") (name "unconnected-(J2-PadA5)") (class "Default")
      (node (ref "J2") (pin "A5") (pinfunction "A5_A5") (pintype "bidirectional"))
    )
    (net (code "71") (name "unconnected-(J2-PadA7)") (class "Default")
      (node (ref "J2") (pin "A7") (pinfunction "A7_A7") (pintype "bidirectional"))
    )
    (net (code "72") (name "unconnected-(J2-PadB2)") (class "Default")
      (node (ref "J2") (pin "B2") (pinfunction "B2_B2") (pintype "bidirectional"))
    )
    (net (code "73") (name "unconnected-(J2-PadB4)") (class "Default")
      (node (ref "J2") (pin "B4") (pinfunction "B4_B4") (pintype "bidirectional"))
    )
    (net (code "74") (name "unconnected-(J2-PadB5)") (class "Default")
      (node (ref "J2") (pin "B5") (pinfunction "B5_B5") (pintype "bidirectional"))
    )
    (net (code "75") (name "unconnected-(J2-PadB6)") (class "Default")
      (node (ref "J2") (pin "B6") (pinfunction "B6_B6") (pintype "bidirectional"))
    )
    (net (code "76") (name "unconnected-(J2-PadB7)") (class "Default")
      (node (ref "J2") (pin "B7") (pinfunction "B7_B7") (pintype "bidirectional"))
    )
    (net (code "77") (name "unconnected-(J2-PadB8)") (class "Default")
      (node (ref "J2") (pin "B8") (pinfunction "B8_B8") (pintype "bidirectional"))
    )
    (net (code "78") (name "unconnected-(J2-PadC2)") (class "Default")
      (node (ref "J2") (pin "C2") (pinfunction "C2_C2") (pintype "bidirectional"))
    )
    (net (code "79") (name "unconnected-(J2-PadC4)") (class "Default")
      (node (ref "J2") (pin "C4") (pinfunction "C4_C4") (pintype "bidirectional"))
    )
    (net (code "80") (name "unconnected-(J2-PadC6)") (class "Default")
      (node (ref "J2") (pin "C6") (pinfunction "C6_C6") (pintype "bidirectional"))
    )
    (net (code "81") (name "unconnected-(J2-PadC8)") (class "Default")
      (node (ref "J2") (pin "C8") (pinfunction "C8_C8") (pintype "bidirectional"))
    )
    (net (code "82") (name "unconnected-(J2-PadD3)") (class "Default")
      (node (ref "J2") (pin "D3") (pinfunction "D3_D3") (pintype "bidirectional"))
    )
    (net (code "83") (name "unconnected-(J2-PadD5)") (class "Default")
      (node (ref "J2") (pin "D5") (pinfunction "D5_D5") (pintype "bidirectional"))
    )
    (net (code "84") (name "unconnected-(J2-PadD7)") (class "Default")
      (node (ref "J2") (pin "D7") (pinfunction "D7_D7") (pintype "bidirectional"))
    )
    (net (code "85") (name "unconnected-(J2-PadE2)") (class "Default")
      (node (ref "J2") (pin "E2") (pinfunction "E2_E2") (pintype "bidirectional"))
    )
    (net (code "86") (name "unconnected-(J2-PadE3)") (class "Default")
      (node (ref "J2") (pin "E3") (pinfunction "E3_E3") (pintype "bidirectional"))
    )
    (net (code "87") (name "unconnected-(J2-PadE4)") (class "Default")
      (node (ref "J2") (pin "E4") (pinfunction "E4_E4") (pintype "bidirectional"))
    )
    (net (code "88") (name "unconnected-(J2-PadE5)") (class "Default")
      (node (ref "J2") (pin "E5") (pinfunction "E5_E5") (pintype "bidirectional"))
    )
    (net (code "89") (name "unconnected-(J2-PadE6)") (class "Default")
      (node (ref "J2") (pin "E6") (pinfunction "E6_E6") (pintype "bidirectional"))
    )
    (net (code "90") (name "unconnected-(J2-PadE7)") (class "Default")
      (node (ref "J2") (pin "E7") (pinfunction "E7_E7") (pintype "bidirectional"))
    )
    (net (code "91") (name "unconnected-(J2-PadE8)") (class "Default")
      (node (ref "J2") (pin "E8") (pinfunction "E8_E8") (pintype "bidirectional"))
    )
    (net (code "92") (name "unconnected-(J2-PadF2)") (class "Default")
      (node (ref "J2") (pin "F2") (pinfunction "F2_F2") (pintype "bidirectional"))
    )
    (net (code "93") (name "unconnected-(J2-PadF4)") (class "Default")
      (node (ref "J2") (pin "F4") (pinfunction "F4_F4") (pintype "bidirectional"))
    )
    (net (code "94") (name "unconnected-(J2-PadF6)") (class "Default")
      (node (ref "J2") (pin "F6") (pinfunction "F6_F6") (pintype "bidirectional"))
    )
    (net (code "95") (name "unconnected-(J2-PadF8)") (class "Default")
      (node (ref "J2") (pin "F8") (pinfunction "F8_F8") (pintype "bidirectional"))
    )
    (net (code "96") (name "unconnected-(J2-PadG3)") (class "Default")
      (node (ref "J2") (pin "G3") (pinfunction "G3_G3") (pintype "bidirectional"))
    )
    (net (code "97") (name "unconnected-(J2-PadG5)") (class "Default")
      (node (ref "J2") (pin "G5") (pinfunction "G5_G5") (pintype "bidirectional"))
    )
    (net (code "98") (name "unconnected-(J2-PadG7)") (class "Default")
      (node (ref "J2") (pin "G7") (pinfunction "G7_G7") (pintype "bidirectional"))
    )
    (net (code "99") (name "unconnected-(J2-PadH2)") (class "Default")
      (node (ref "J2") (pin "H2") (pinfunction "H2_H2") (pintype "bidirectional"))
    )
    (net (code "100") (name "unconnected-(J2-PadH3)") (class "Default")
      (node (ref "J2") (pin "H3") (pinfunction "H3_H3") (pintype "bidirectional"))
    )
    (net (code "101") (name "unconnected-(J2-PadH4)") (class "Default")
      (node (ref "J2") (pin "H4") (pinfunction "H4_H4") (pintype "bidirectional"))
    )
    (net (code "102") (name "unconnected-(J2-PadH5)") (class "Default")
      (node (ref "J2") (pin "H5") (pinfunction "H5_H5") (pintype "bidirectional"))
    )
    (net (code "103") (name "unconnected-(J2-PadH6)") (class "Default")
      (node (ref "J2") (pin "H6") (pinfunction "H6_H6") (pintype "bidirectional"))
    )
    (net (code "104") (name "unconnected-(J2-PadH7)") (class "Default")
      (node (ref "J2") (pin "H7") (pinfunction "H7_H7") (pintype "bidirectional"))
    )
    (net (code "105") (name "unconnected-(J2-PadH8)") (class "Default")
      (node (ref "J2") (pin "H8") (pinfunction "H8_H8") (pintype "bidirectional"))
    )
    (net (code "106") (name "unconnected-(J2-PadI2)") (class "Default")
      (node (ref "J2") (pin "I2") (pinfunction "I2_I2") (pintype "bidirectional"))
    )
    (net (code "107") (name "unconnected-(J2-PadI4)") (class "Default")
      (node (ref "J2") (pin "I4") (pinfunction "I4_I4") (pintype "bidirectional"))
    )
    (net (code "108") (name "unconnected-(J2-PadI6)") (class "Default")
      (node (ref "J2") (pin "I6") (pinfunction "I6_I6") (pintype "bidirectional"))
    )
    (net (code "109") (name "unconnected-(J2-PadI8)") (class "Default")
      (node (ref "J2") (pin "I8") (pinfunction "I8_I8") (pintype "bidirectional"))
    )
    (net (code "110") (name "unconnected-(J2-PadJ3)") (class "Default")
      (node (ref "J2") (pin "J3") (pinfunction "J3_J3") (pintype "bidirectional"))
    )
    (net (code "111") (name "unconnected-(J2-PadJ5)") (class "Default")
      (node (ref "J2") (pin "J5") (pinfunction "J5_J5") (pintype "bidirectional"))
    )
    (net (code "112") (name "unconnected-(J2-PadJ7)") (class "Default")
      (node (ref "J2") (pin "J7") (pinfunction "J7_J7") (pintype "bidirectional"))
    )
    (net (code "113") (name "unconnected-(J2-PadK2)") (class "Default")
      (node (ref "J2") (pin "K2") (pinfunction "K2_K2") (pintype "bidirectional"))
    )
    (net (code "114") (name "unconnected-(J2-PadK3)") (class "Default")
      (node (ref "J2") (pin "K3") (pinfunction "K3_K3") (pintype "bidirectional"))
    )
    (net (code "115") (name "unconnected-(J2-PadK4)") (class "Default")
      (node (ref "J2") (pin "K4") (pinfunction "K4_K4") (pintype "bidirectional"))
    )
    (net (code "116") (name "unconnected-(J2-PadK5)") (class "Default")
      (node (ref "J2") (pin "K5") (pinfunction "K5_K5") (pintype "bidirectional"))
    )
    (net (code "117") (name "unconnected-(J2-PadK6)") (class "Default")
      (node (ref "J2") (pin "K6") (pinfunction "K6_K6") (pintype "bidirectional"))
    )
    (net (code "118") (name "unconnected-(J2-PadK7)") (class "Default")
      (node (ref "J2") (pin "K7") (pinfunction "K7_K7") (pintype "bidirectional"))
    )
    (net (code "119") (name "unconnected-(J2-PadK8)") (class "Default")
      (node (ref "J2") (pin "K8") (pinfunction "K8_K8") (pintype "bidirectional"))
    )
    (net (code "120") (name "unconnected-(J2-PadL2)") (class "Default")
      (node (ref "J2") (pin "L2") (pinfunction "L2_L2") (pintype "bidirectional"))
    )
    (net (code "121") (name "unconnected-(J2-PadL4)") (class "Default")
      (node (ref "J2") (pin "L4") (pinfunction "L4_L4") (pintype "bidirectional"))
    )
    (net (code "122") (name "unconnected-(J2-PadL6)") (class "Default")
      (node (ref "J2") (pin "L6") (pinfunction "L6_L6") (pintype "bidirectional"))
    )
    (net (code "123") (name "unconnected-(J2-PadL8)") (class "Default")
      (node (ref "J2") (pin "L8") (pinfunction "L8_L8") (pintype "bidirectional"))
    )
    (net (code "124") (name "unconnected-(J8-PadA5)") (class "Default")
      (node (ref "J8") (pin "A5") (pinfunction "A5_A5") (pintype "bidirectional"))
    )
    (net (code "125") (name "unconnected-(J8-PadB1)") (class "Default")
      (node (ref "J8") (pin "B1") (pinfunction "B1_B1") (pintype "bidirectional+no_connect"))
    )
    (net (code "126") (name "unconnected-(J8-PadB5)") (class "Default")
      (node (ref "J8") (pin "B5") (pinfunction "B5_B5") (pintype "bidirectional"))
    )
    (net (code "127") (name "unconnected-(J8-PadD5)") (class "Default")
      (node (ref "J8") (pin "D5") (pinfunction "D5_D5") (pintype "bidirectional"))
    )
    (net (code "128") (name "unconnected-(J8-PadE4)") (class "Default")
      (node (ref "J8") (pin "E4") (pinfunction "E4_E4") (pintype "bidirectional"))
    )
    (net (code "129") (name "unconnected-(J8-PadE5)") (class "Default")
      (node (ref "J8") (pin "E5") (pinfunction "E5_E5") (pintype "bidirectional"))
    )
    (net (code "130") (name "unconnected-(J8-PadF4)") (class "Default")
      (node (ref "J8") (pin "F4") (pinfunction "F4_F4") (pintype "bidirectional"))
    )
    (net (code "131") (name "unconnected-(J8-PadG3)") (class "Default")
      (node (ref "J8") (pin "G3") (pinfunction "G3_G3") (pintype "bidirectional"))
    )
    (net (code "132") (name "unconnected-(J8-PadH3)") (class "Default")
      (node (ref "J8") (pin "H3") (pinfunction "H3_H3") (pintype "bidirectional"))
    )
    (net (code "133") (name "unconnected-(J8-PadI2)") (class "Default")
      (node (ref "J8") (pin "I2") (pinfunction "I2_I2") (pintype "bidirectional"))
    )
    (net (code "134") (name "unconnected-(J8-PadJ3)") (class "Default")
      (node (ref "J8") (pin "J3") (pinfunction "J3_J3") (pintype "bidirectional"))
    )
    (net (code "135") (name "unconnected-(J8-PadK3)") (class "Default")
      (node (ref "J8") (pin "K3") (pinfunction "K3_K3") (pintype "bidirectional"))
    )
    (net (code "136") (name "unconnected-(J8-PadL2)") (class "Default")
      (node (ref "J8") (pin "L2") (pinfunction "L2_L2") (pintype "bidirectional+no_connect"))
    )
    (net (code "137") (name "unconnected-(J9-PadA3)") (class "Default")
      (node (ref "J9") (pin "A3") (pinfunction "A3_A3") (pintype "bidirectional+no_connect"))
    )
    (net (code "138") (name "unconnected-(J9-PadA5)") (class "Default")
      (node (ref "J9") (pin "A5") (pinfunction "A5_A5") (pintype "bidirectional+no_connect"))
    )
    (net (code "139") (name "unconnected-(J9-PadA7)") (class "Default")
      (node (ref "J9") (pin "A7") (pinfunction "A7_A7") (pintype "bidirectional+no_connect"))
    )
    (net (code "140") (name "unconnected-(J9-PadA8)") (class "Default")
      (node (ref "J9") (pin "A8") (pinfunction "A8_A8") (pintype "bidirectional+no_connect"))
    )
    (net (code "141") (name "unconnected-(J9-PadB2)") (class "Default")
      (node (ref "J9") (pin "B2") (pinfunction "B2_B2") (pintype "bidirectional+no_connect"))
    )
    (net (code "142") (name "unconnected-(J9-PadB3)") (class "Default")
      (node (ref "J9") (pin "B3") (pinfunction "B3_B3") (pintype "bidirectional+no_connect"))
    )
    (net (code "143") (name "unconnected-(J9-PadB4)") (class "Default")
      (node (ref "J9") (pin "B4") (pinfunction "B4_B4") (pintype "bidirectional+no_connect"))
    )
    (net (code "144") (name "unconnected-(J9-PadB5)") (class "Default")
      (node (ref "J9") (pin "B5") (pinfunction "B5_B5") (pintype "bidirectional+no_connect"))
    )
    (net (code "145") (name "unconnected-(J9-PadB6)") (class "Default")
      (node (ref "J9") (pin "B6") (pinfunction "B6_B6") (pintype "bidirectional+no_connect"))
    )
    (net (code "146") (name "unconnected-(J9-PadB7)") (class "Default")
      (node (ref "J9") (pin "B7") (pinfunction "B7_B7") (pintype "bidirectional+no_connect"))
    )
    (net (code "147") (name "unconnected-(J9-PadB8)") (class "Default")
      (node (ref "J9") (pin "B8") (pinfunction "B8_B8") (pintype "bidirectional+no_connect"))
    )
    (net (code "148") (name "unconnected-(J9-PadC2)") (class "Default")
      (node (ref "J9") (pin "C2") (pinfunction "C2_C2") (pintype "bidirectional+no_connect"))
    )
    (net (code "149") (name "unconnected-(J9-PadC4)") (class "Default")
      (node (ref "J9") (pin "C4") (pinfunction "C4_C4") (pintype "bidirectional+no_connect"))
    )
    (net (code "150") (name "unconnected-(J9-PadC6)") (class "Default")
      (node (ref "J9") (pin "C6") (pinfunction "C6_C6") (pintype "bidirectional+no_connect"))
    )
    (net (code "151") (name "unconnected-(J9-PadC8)") (class "Default")
      (node (ref "J9") (pin "C8") (pinfunction "C8_C8") (pintype "bidirectional+no_connect"))
    )
    (net (code "152") (name "unconnected-(J9-PadD3)") (class "Default")
      (node (ref "J9") (pin "D3") (pinfunction "D3_D3") (pintype "bidirectional+no_connect"))
    )
    (net (code "153") (name "unconnected-(J9-PadD5)") (class "Default")
      (node (ref "J9") (pin "D5") (pinfunction "D5_D5") (pintype "bidirectional+no_connect"))
    )
    (net (code "154") (name "unconnected-(J9-PadD7)") (class "Default")
      (node (ref "J9") (pin "D7") (pinfunction "D7_D7") (pintype "bidirectional+no_connect"))
    )
    (net (code "155") (name "unconnected-(J9-PadD8)") (class "Default")
      (node (ref "J9") (pin "D8") (pinfunction "D8_D8") (pintype "bidirectional+no_connect"))
    )
    (net (code "156") (name "unconnected-(J9-PadE2)") (class "Default")
      (node (ref "J9") (pin "E2") (pinfunction "E2_E2") (pintype "bidirectional+no_connect"))
    )
    (net (code "157") (name "unconnected-(J9-PadE3)") (class "Default")
      (node (ref "J9") (pin "E3") (pinfunction "E3_E3") (pintype "bidirectional+no_connect"))
    )
    (net (code "158") (name "unconnected-(J9-PadE4)") (class "Default")
      (node (ref "J9") (pin "E4") (pinfunction "E4_E4") (pintype "bidirectional+no_connect"))
    )
    (net (code "159") (name "unconnected-(J9-PadE5)") (class "Default")
      (node (ref "J9") (pin "E5") (pinfunction "E5_E5") (pintype "bidirectional+no_connect"))
    )
    (net (code "160") (name "unconnected-(J9-PadE6)") (class "Default")
      (node (ref "J9") (pin "E6") (pinfunction "E6_E6") (pintype "bidirectional+no_connect"))
    )
    (net (code "161") (name "unconnected-(J9-PadE7)") (class "Default")
      (node (ref "J9") (pin "E7") (pinfunction "E7_E7") (pintype "bidirectional+no_connect"))
    )
    (net (code "162") (name "unconnected-(J9-PadE8)") (class "Default")
      (node (ref "J9") (pin "E8") (pinfunction "E8_E8") (pintype "bidirectional+no_connect"))
    )
    (net (code "163") (name "unconnected-(J9-PadF2)") (class "Default")
      (node (ref "J9") (pin "F2") (pinfunction "F2_F2") (pintype "bidirectional+no_connect"))
    )
    (net (code "164") (name "unconnected-(J9-PadF4)") (class "Default")
      (node (ref "J9") (pin "F4") (pinfunction "F4_F4") (pintype "bidirectional+no_connect"))
    )
    (net (code "165") (name "unconnected-(J9-PadF6)") (class "Default")
      (node (ref "J9") (pin "F6") (pinfunction "F6_F6") (pintype "bidirectional+no_connect"))
    )
    (net (code "166") (name "unconnected-(J9-PadF8)") (class "Default")
      (node (ref "J9") (pin "F8") (pinfunction "F8_F8") (pintype "bidirectional+no_connect"))
    )
    (net (code "167") (name "unconnected-(J9-PadG3)") (class "Default")
      (node (ref "J9") (pin "G3") (pinfunction "G3_G3") (pintype "bidirectional+no_connect"))
    )
    (net (code "168") (name "unconnected-(J9-PadG5)") (class "Default")
      (node (ref "J9") (pin "G5") (pinfunction "G5_G5") (pintype "bidirectional+no_connect"))
    )
    (net (code "169") (name "unconnected-(J9-PadG7)") (class "Default")
      (node (ref "J9") (pin "G7") (pinfunction "G7_G7") (pintype "bidirectional+no_connect"))
    )
    (net (code "170") (name "unconnected-(J9-PadH2)") (class "Default")
      (node (ref "J9") (pin "H2") (pinfunction "H2_H2") (pintype "bidirectional+no_connect"))
    )
    (net (code "171") (name "unconnected-(J9-PadH3)") (class "Default")
      (node (ref "J9") (pin "H3") (pinfunction "H3_H3") (pintype "bidirectional+no_connect"))
    )
    (net (code "172") (name "unconnected-(J9-PadH4)") (class "Default")
      (node (ref "J9") (pin "H4") (pinfunction "H4_H4") (pintype "bidirectional+no_connect"))
    )
    (net (code "173") (name "unconnected-(J9-PadH5)") (class "Default")
      (node (ref "J9") (pin "H5") (pinfunction "H5_H5") (pintype "bidirectional+no_connect"))
    )
    (net (code "174") (name "unconnected-(J9-PadH6)") (class "Default")
      (node (ref "J9") (pin "H6") (pinfunction "H6_H6") (pintype "bidirectional+no_connect"))
    )
    (net (code "175") (name "unconnected-(J9-PadH7)") (class "Default")
      (node (ref "J9") (pin "H7") (pinfunction "H7_H7") (pintype "bidirectional+no_connect"))
    )
    (net (code "176") (name "unconnected-(J9-PadH8)") (class "Default")
      (node (ref "J9") (pin "H8") (pinfunction "H8_H8") (pintype "bidirectional+no_connect"))
    )
    (net (code "177") (name "unconnected-(J9-PadI2)") (class "Default")
      (node (ref "J9") (pin "I2") (pinfunction "I2_I2") (pintype "bidirectional+no_connect"))
    )
    (net (code "178") (name "unconnected-(J9-PadI4)") (class "Default")
      (node (ref "J9") (pin "I4") (pinfunction "I4_I4") (pintype "bidirectional+no_connect"))
    )
    (net (code "179") (name "unconnected-(J9-PadI6)") (class "Default")
      (node (ref "J9") (pin "I6") (pinfunction "I6_I6") (pintype "bidirectional+no_connect"))
    )
    (net (code "180") (name "unconnected-(J9-PadI8)") (class "Default")
      (node (ref "J9") (pin "I8") (pinfunction "I8_I8") (pintype "bidirectional+no_connect"))
    )
    (net (code "181") (name "unconnected-(J9-PadJ3)") (class "Default")
      (node (ref "J9") (pin "J3") (pinfunction "J3_J3") (pintype "bidirectional+no_connect"))
    )
    (net (code "182") (name "unconnected-(J9-PadJ5)") (class "Default")
      (node (ref "J9") (pin "J5") (pinfunction "J5_J5") (pintype "bidirectional+no_connect"))
    )
    (net (code "183") (name "unconnected-(J9-PadJ7)") (class "Default")
      (node (ref "J9") (pin "J7") (pinfunction "J7_J7") (pintype "bidirectional+no_connect"))
    )
    (net (code "184") (name "unconnected-(J9-PadK2)") (class "Default")
      (node (ref "J9") (pin "K2") (pinfunction "K2_K2") (pintype "bidirectional+no_connect"))
    )
    (net (code "185") (name "unconnected-(J9-PadK3)") (class "Default")
      (node (ref "J9") (pin "K3") (pinfunction "K3_K3") (pintype "bidirectional+no_connect"))
    )
    (net (code "186") (name "unconnected-(J9-PadK4)") (class "Default")
      (node (ref "J9") (pin "K4") (pinfunction "K4_K4") (pintype "bidirectional+no_connect"))
    )
    (net (code "187") (name "unconnected-(J9-PadK5)") (class "Default")
      (node (ref "J9") (pin "K5") (pinfunction "K5_K5") (pintype "bidirectional+no_connect"))
    )
    (net (code "188") (name "unconnected-(J9-PadK6)") (class "Default")
      (node (ref "J9") (pin "K6") (pinfunction "K6_K6") (pintype "bidirectional+no_connect"))
    )
    (net (code "189") (name "unconnected-(J9-PadK7)") (class "Default")
      (node (ref "J9") (pin "K7") (pinfunction "K7_K7") (pintype "bidirectional+no_connect"))
    )
    (net (code "190") (name "unconnected-(J9-PadK8)") (class "Default")
      (node (ref "J9") (pin "K8") (pinfunction "K8_K8") (pintype "bidirectional+no_connect"))
    )
    (net (code "191") (name "unconnected-(J9-PadL2)") (class "Default")
      (node (ref "J9") (pin "L2") (pinfunction "L2_L2") (pintype "bidirectional+no_connect"))
    )
    (net (code "192") (name "unconnected-(J9-PadL4)") (class "Default")
      (node (ref "J9") (pin "L4") (pinfunction "L4_L4") (pintype "bidirectional+no_connect"))
    )
    (net (code "193") (name "unconnected-(J9-PadL6)") (class "Default")
      (node (ref "J9") (pin "L6") (pinfunction "L6_L6") (pintype "bidirectional+no_connect"))
    )
    (net (code "194") (name "unconnected-(J9-PadL8)") (class "Default")
      (node (ref "J9") (pin "L8") (pinfunction "L8_L8") (pintype "bidirectional+no_connect"))
    )
  )
)
